# RFR24_AMS_Design_-_Thermistors_V1.net
KiCad netlist of a schematic drawn in Altium Designer
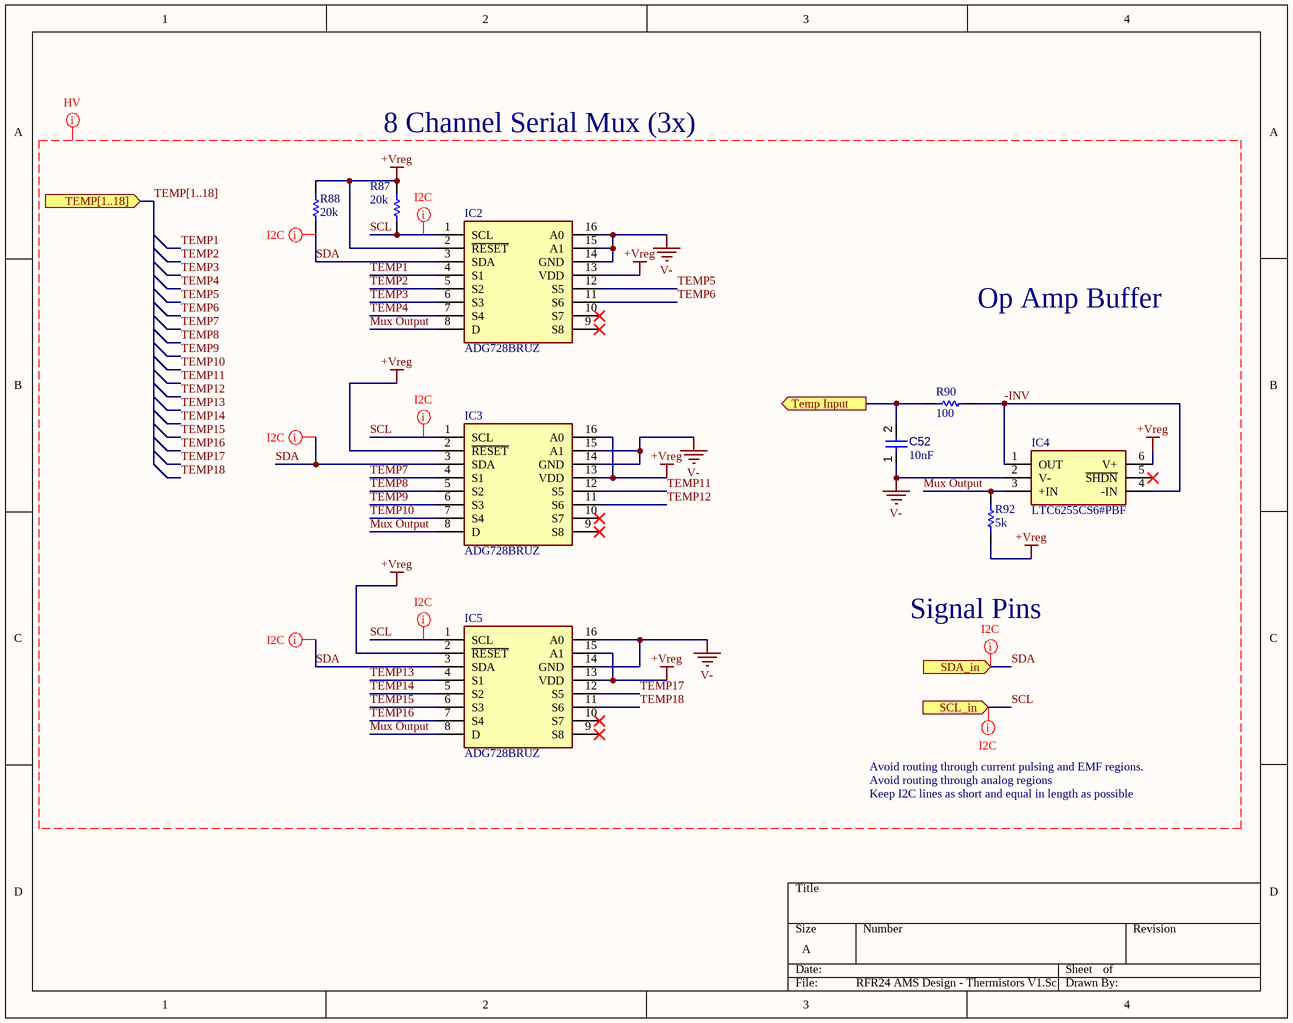
[diagram p0: RFR24 AMS Design - Thermistors V1.SchDoc]

(export (version "E")
  (design (tool "Eeschema 10.0.6"))
  (components
    (comp (ref "C52")
      (value "10nF")
      (footprint "CAPC2013X145X50LL20T25")
      (description "Chip Capacitor, 1 uF, +/-10%, 25 V, 0805 (2012 Metric)")
      (fields (field (name "TOLERANCE") "10%") (field (name "Comment") "Capacitor 1 uF +/- 10% 25 V 0805"))
      (libsource (lib "Rutgers University") (part "CAP-NP-2"))
    )
    (comp (ref "IC2")
      (value "ADG728BRUZ")
      (footprint "SamacSys:SOP65P640X120-16N")
      (description "Integrated Circuit")
      (fields (field (name "MOUSER PART NUMBER") "584-ADG728BRUZ"))
      (libsource (lib "*") (part "ADG728BRUZ"))
    )
    (comp (ref "IC3")
      (value "ADG728BRUZ")
      (footprint "SamacSys:SOP65P640X120-16N")
      (description "Integrated Circuit")
      (fields (field (name "MOUSER PART NUMBER") "584-ADG728BRUZ"))
      (libsource (lib "*") (part "ADG728BRUZ"))
    )
    (comp (ref "IC4")
      (value "LTC6255CS6#PBF")
      (footprint "SamacSys:SOT95P280X100-6N")
      (description "Integrated Circuit")
      (libsource (lib "*") (part "LTC6255CS6#PBF"))
    )
    (comp (ref "IC5")
      (value "ADG728BRUZ")
      (footprint "SamacSys:SOP65P640X120-16N")
      (description "Integrated Circuit")
      (fields (field (name "MOUSER PART NUMBER") "584-ADG728BRUZ"))
      (libsource (lib "*") (part "ADG728BRUZ"))
    )
    (comp (ref "R87")
      (value "20k")
      (footprint "RESC2013X70X40LL20T20")
      (description "Chip Resistor, 1 KOhm, +/- 1%, 0.125 W, -55 to 155 degC, 0805 (2013 Metric)")
      (fields (field (name "TOLERANCE") "1%") (field (name "POWER") "125mW"))
      (libsource (lib "Rutgers University") (part "RES-2"))
    )
    (comp (ref "R88")
      (value "20k")
      (footprint "RESC2013X70X40LL20T20")
      (description "Chip Resistor, 1 KOhm, +/- 1%, 0.125 W, -55 to 155 degC, 0805 (2013 Metric)")
      (fields (field (name "TOLERANCE") "1%") (field (name "POWER") "125mW"))
      (libsource (lib "Rutgers University") (part "RES-2"))
    )
    (comp (ref "R90")
      (value "100")
      (footprint "RESC2013X70X40LL20T20")
      (description "Chip Resistor, 1 KOhm, +/- 1%, 0.125 W, -55 to 155 degC, 0805 (2013 Metric)")
      (fields (field (name "TOLERANCE") "1%") (field (name "POWER") "125mW"))
      (libsource (lib "Rutgers University") (part "RES-2"))
    )
    (comp (ref "R92")
      (value "5k")
      (footprint "RESC2013X70X40LL20T20")
      (description "Chip Resistor, 1 KOhm, +/- 1%, 0.125 W, -55 to 155 degC, 0805 (2013 Metric)")
      (fields (field (name "TOLERANCE") "1%") (field (name "POWER") "125mW"))
      (libsource (lib "Rutgers University") (part "RES-2"))
    )
  )
  (nets
    (net (code "1") (name "+Vreg") (class "Default")
      (node (ref "IC2") (pin "13") (pinfunction "VDD_13") (pintype "passive"))
      (node (ref "IC2") (pin "2") (pinfunction "~{RESET}_2") (pintype "passive"))
      (node (ref "IC3") (pin "13") (pinfunction "VDD_13") (pintype "passive"))
      (node (ref "IC3") (pin "16") (pinfunction "A0_16") (pintype "passive"))
      (node (ref "IC3") (pin "2") (pinfunction "~{RESET}_2") (pintype "passive"))
      (node (ref "IC4") (pin "6") (pinfunction "V+_6") (pintype "passive"))
      (node (ref "IC5") (pin "13") (pinfunction "VDD_13") (pintype "passive"))
      (node (ref "IC5") (pin "15") (pinfunction "A1_15") (pintype "passive"))
      (node (ref "IC5") (pin "2") (pinfunction "~{RESET}_2") (pintype "passive"))
      (node (ref "R87") (pin "2") (pinfunction "2_2") (pintype "passive"))
      (node (ref "R88") (pin "2") (pinfunction "2_2") (pintype "passive"))
      (node (ref "R92") (pin "1") (pinfunction "1_1") (pintype "passive"))
    )
    (net (code "2") (name "/-INV") (class "Default")
      (node (ref "IC4") (pin "1") (pinfunction "OUT_1") (pintype "passive"))
      (node (ref "IC4") (pin "4") (pinfunction "-IN_4") (pintype "passive"))
      (node (ref "R90") (pin "1") (pinfunction "1_1") (pintype "passive"))
    )
    (net (code "3") (name "/Mux Output") (class "Default")
      (node (ref "IC2") (pin "8") (pinfunction "D_8") (pintype "passive"))
      (node (ref "IC3") (pin "8") (pinfunction "D_8") (pintype "passive"))
      (node (ref "IC4") (pin "3") (pinfunction "+IN_3") (pintype "passive"))
      (node (ref "IC5") (pin "8") (pinfunction "D_8") (pintype "passive"))
      (node (ref "R92") (pin "2") (pinfunction "2_2") (pintype "passive"))
    )
    (net (code "4") (name "/SCL") (class "Default")
      (node (ref "IC2") (pin "1") (pinfunction "SCL_1") (pintype "passive"))
      (node (ref "IC3") (pin "1") (pinfunction "SCL_1") (pintype "passive"))
      (node (ref "IC5") (pin "1") (pinfunction "SCL_1") (pintype "passive"))
      (node (ref "R87") (pin "1") (pinfunction "1_1") (pintype "passive"))
    )
    (net (code "5") (name "/SDA") (class "Default")
      (node (ref "IC2") (pin "3") (pinfunction "SDA_3") (pintype "passive"))
      (node (ref "IC3") (pin "3") (pinfunction "SDA_3") (pintype "passive"))
      (node (ref "IC5") (pin "3") (pinfunction "SDA_3") (pintype "passive"))
      (node (ref "R88") (pin "1") (pinfunction "1_1") (pintype "passive"))
    )
    (net (code "6") (name "/TEMP1") (class "Default")
      (node (ref "IC2") (pin "4") (pinfunction "S1_4") (pintype "passive"))
    )
    (net (code "7") (name "/TEMP2") (class "Default")
      (node (ref "IC2") (pin "5") (pinfunction "S2_5") (pintype "passive"))
    )
    (net (code "8") (name "/TEMP3") (class "Default")
      (node (ref "IC2") (pin "6") (pinfunction "S3_6") (pintype "passive"))
    )
    (net (code "9") (name "/TEMP4") (class "Default")
      (node (ref "IC2") (pin "7") (pinfunction "S4_7") (pintype "passive"))
    )
    (net (code "10") (name "/TEMP5") (class "Default")
      (node (ref "IC2") (pin "12") (pinfunction "S5_12") (pintype "passive"))
    )
    (net (code "11") (name "/TEMP6") (class "Default")
      (node (ref "IC2") (pin "11") (pinfunction "S6_11") (pintype "passive"))
    )
    (net (code "12") (name "/TEMP7") (class "Default")
      (node (ref "IC3") (pin "4") (pinfunction "S1_4") (pintype "passive"))
    )
    (net (code "13") (name "/TEMP8") (class "Default")
      (node (ref "IC3") (pin "5") (pinfunction "S2_5") (pintype "passive"))
    )
    (net (code "14") (name "/TEMP9") (class "Default")
      (node (ref "IC3") (pin "6") (pinfunction "S3_6") (pintype "passive"))
    )
    (net (code "15") (name "/TEMP10") (class "Default")
      (node (ref "IC3") (pin "7") (pinfunction "S4_7") (pintype "passive"))
    )
    (net (code "16") (name "/TEMP11") (class "Default")
      (node (ref "IC3") (pin "12") (pinfunction "S5_12") (pintype "passive"))
    )
    (net (code "17") (name "/TEMP12") (class "Default")
      (node (ref "IC3") (pin "11") (pinfunction "S6_11") (pintype "passive"))
    )
    (net (code "18") (name "/TEMP13") (class "Default")
      (node (ref "IC5") (pin "4") (pinfunction "S1_4") (pintype "passive"))
    )
    (net (code "19") (name "/TEMP14") (class "Default")
      (node (ref "IC5") (pin "5") (pinfunction "S2_5") (pintype "passive"))
    )
    (net (code "20") (name "/TEMP15") (class "Default")
      (node (ref "IC5") (pin "6") (pinfunction "S3_6") (pintype "passive"))
    )
    (net (code "21") (name "/TEMP16") (class "Default")
      (node (ref "IC5") (pin "7") (pinfunction "S4_7") (pintype "passive"))
    )
    (net (code "22") (name "/TEMP17") (class "Default")
      (node (ref "IC5") (pin "12") (pinfunction "S5_12") (pintype "passive"))
    )
    (net (code "23") (name "/TEMP18") (class "Default")
      (node (ref "IC5") (pin "11") (pinfunction "S6_11") (pintype "passive"))
    )
    (net (code "25") (name "/Temp Input") (class "Default")
      (node (ref "C52") (pin "2") (pinfunction "2_2") (pintype "passive"))
      (node (ref "R90") (pin "2") (pinfunction "2_2") (pintype "passive"))
    )
    (net (code "26") (name "V-") (class "Default")
      (node (ref "C52") (pin "1") (pinfunction "1_1") (pintype "passive"))
      (node (ref "IC2") (pin "14") (pinfunction "GND_14") (pintype "passive"))
      (node (ref "IC2") (pin "15") (pinfunction "A1_15") (pintype "passive"))
      (node (ref "IC2") (pin "16") (pinfunction "A0_16") (pintype "passive"))
      (node (ref "IC3") (pin "14") (pinfunction "GND_14") (pintype "passive"))
      (node (ref "IC3") (pin "15") (pinfunction "A1_15") (pintype "passive"))
      (node (ref "IC4") (pin "2") (pinfunction "V-_2") (pintype "passive"))
      (node (ref "IC5") (pin "14") (pinfunction "GND_14") (pintype "passive"))
      (node (ref "IC5") (pin "16") (pinfunction "A0_16") (pintype "passive"))
    )
    (net (code "27") (name "unconnected-(IC2-S7-Pad10)") (class "Default")
      (node (ref "IC2") (pin "10") (pinfunction "S7_10") (pintype "passive+no_connect"))
    )
    (net (code "28") (name "unconnected-(IC2-S8-Pad9)") (class "Default")
      (node (ref "IC2") (pin "9") (pinfunction "S8_9") (pintype "passive+no_connect"))
    )
    (net (code "29") (name "unconnected-(IC3-S7-Pad10)") (class "Default")
      (node (ref "IC3") (pin "10") (pinfunction "S7_10") (pintype "passive+no_connect"))
    )
    (net (code "30") (name "unconnected-(IC3-S8-Pad9)") (class "Default")
      (node (ref "IC3") (pin "9") (pinfunction "S8_9") (pintype "passive+no_connect"))
    )
    (net (code "31") (name "unconnected-(IC4-~{SHDN}-Pad5)") (class "Default")
      (node (ref "IC4") (pin "5") (pinfunction "~{SHDN}_5") (pintype "passive+no_connect"))
    )
    (net (code "32") (name "unconnected-(IC5-S7-Pad10)") (class "Default")
      (node (ref "IC5") (pin "10") (pinfunction "S7_10") (pintype "passive+no_connect"))
    )
    (net (code "33") (name "unconnected-(IC5-S8-Pad9)") (class "Default")
      (node (ref "IC5") (pin "9") (pinfunction "S8_9") (pintype "passive+no_connect"))
    )
  )
)
